# USB2RS485.net
KiCad netlist of a schematic drawn in Altium Designer
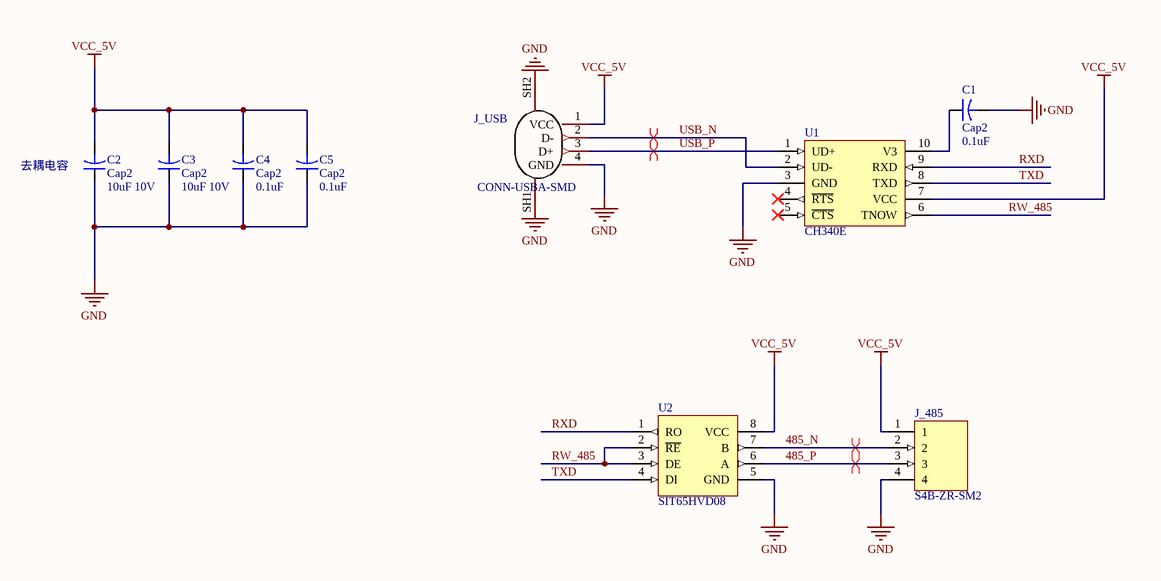
[diagram p0: USB2RS485.SchDoc]

(export (version "E")
  (design (tool "Eeschema 10.0.6"))
  (components
    (comp (ref "C1")
      (value "Cap2")
      (footprint "CAPR5-4X5")
      (description "Capacitor")
      (fields (field (name "ALTIUM_VALUE") "0.1uF") (field (name "PUBLISHER") "Altium Limited"))
      (libsource (lib "Miscellaneous Devices") (part "Cap2"))
    )
    (comp (ref "C2")
      (value "Cap2")
      (footprint "CAPR5-4X5")
      (description "Capacitor")
      (fields (field (name "ALTIUM_VALUE") "10uF 10V") (field (name "PUBLISHER") "Altium Limited"))
      (libsource (lib "Miscellaneous Devices") (part "Cap2"))
    )
    (comp (ref "C3")
      (value "Cap2")
      (footprint "CAPR5-4X5")
      (description "Capacitor")
      (fields (field (name "ALTIUM_VALUE") "10uF 10V") (field (name "PUBLISHER") "Altium Limited"))
      (libsource (lib "Miscellaneous Devices") (part "Cap2"))
    )
    (comp (ref "C4")
      (value "Cap2")
      (footprint "CAPR5-4X5")
      (description "Capacitor")
      (fields (field (name "ALTIUM_VALUE") "0.1uF") (field (name "PUBLISHER") "Altium Limited"))
      (libsource (lib "Miscellaneous Devices") (part "Cap2"))
    )
    (comp (ref "C5")
      (value "Cap2")
      (footprint "CAPR5-4X5")
      (description "Capacitor")
      (fields (field (name "ALTIUM_VALUE") "0.1uF") (field (name "PUBLISHER") "Altium Limited"))
      (libsource (lib "Miscellaneous Devices") (part "Cap2"))
    )
    (comp (ref "J_485") (value "S4B-ZR-SM2") (footprint "SM2") (libsource (lib "USB2RS485") (part "CONN4B")))
    (comp (ref "J_USB")
      (value "CONN-USBA-SMD")
      (footprint "USB-A-SMD_AF")
      (libsource (lib "USB2RS485") (part "CONN-USB"))
    )
    (comp (ref "U1") (value "CH340E") (footprint "MSOP10") (libsource (lib "USB2RS485") (part "CH340E")))
    (comp (ref "U2")
      (value "SIT65HVD08")
      (footprint "MSOP8")
      (libsource (lib "USB2RS485") (part "SIT65HVD08DGK"))
    )
  )
  (nets
    (net (code "1") (name "/485_N") (class "Default")
      (node (ref "J_485") (pin "2") (pinfunction "2_2") (pintype "input"))
      (node (ref "U2") (pin "7") (pinfunction "B_7") (pintype "output"))
    )
    (net (code "2") (name "/485_P") (class "Default")
      (node (ref "J_485") (pin "3") (pinfunction "3_3") (pintype "input"))
      (node (ref "U2") (pin "6") (pinfunction "A_6") (pintype "output"))
    )
    (net (code "3") (name "/RW_485") (class "Default")
      (node (ref "U1") (pin "6") (pinfunction "TNOW_6") (pintype "output"))
      (node (ref "U2") (pin "2") (pinfunction "~{RE}_2") (pintype "input"))
      (node (ref "U2") (pin "3") (pinfunction "DE_3") (pintype "input"))
    )
    (net (code "4") (name "/RXD") (class "Default")
      (node (ref "U1") (pin "9") (pinfunction "RXD_9") (pintype "input"))
      (node (ref "U2") (pin "1") (pinfunction "RO_1") (pintype "output"))
    )
    (net (code "5") (name "/TXD") (class "Default")
      (node (ref "U1") (pin "8") (pinfunction "TXD_8") (pintype "output"))
      (node (ref "U2") (pin "4") (pinfunction "DI_4") (pintype "input"))
    )
    (net (code "6") (name "/USB_N") (class "Default")
      (node (ref "J_USB") (pin "2") (pinfunction "D-_2") (pintype "output"))
      (node (ref "U1") (pin "2") (pinfunction "UD-_2") (pintype "input"))
    )
    (net (code "7") (name "/USB_P") (class "Default")
      (node (ref "J_USB") (pin "3") (pinfunction "D+_3") (pintype "output"))
      (node (ref "U1") (pin "1") (pinfunction "UD+_1") (pintype "input"))
    )
    (net (code "8") (name "GND") (class "Default")
      (node (ref "C1") (pin "2") (pinfunction "2_2") (pintype "passive"))
      (node (ref "C2") (pin "1") (pinfunction "1_1") (pintype "passive"))
      (node (ref "C3") (pin "1") (pinfunction "1_1") (pintype "passive"))
      (node (ref "C4") (pin "1") (pinfunction "1_1") (pintype "passive"))
      (node (ref "C5") (pin "1") (pinfunction "1_1") (pintype "passive"))
      (node (ref "J_485") (pin "4") (pinfunction "4_4") (pintype "power_in"))
      (node (ref "J_USB") (pin "4") (pinfunction "GND_4") (pintype "power_in"))
      (node (ref "J_USB") (pin "SH1") (pinfunction "SH1_SH1") (pintype "passive"))
      (node (ref "J_USB") (pin "SH2") (pinfunction "SH2_SH2") (pintype "passive"))
      (node (ref "U1") (pin "3") (pinfunction "GND_3") (pintype "power_in"))
      (node (ref "U2") (pin "5") (pinfunction "GND_5") (pintype "power_in"))
    )
    (net (code "9") (name "Net-(U1-V3)") (class "Default")
      (node (ref "C1") (pin "1") (pinfunction "1_1") (pintype "passive"))
      (node (ref "U1") (pin "10") (pinfunction "V3_10") (pintype "power_in"))
    )
    (net (code "10") (name "VCC_5V") (class "Default")
      (node (ref "C2") (pin "2") (pinfunction "2_2") (pintype "passive"))
      (node (ref "C3") (pin "2") (pinfunction "2_2") (pintype "passive"))
      (node (ref "C4") (pin "2") (pinfunction "2_2") (pintype "passive"))
      (node (ref "C5") (pin "2") (pinfunction "2_2") (pintype "passive"))
      (node (ref "J_485") (pin "1") (pinfunction "1_1") (pintype "power_in"))
      (node (ref "J_USB") (pin "1") (pinfunction "VCC_1") (pintype "power_in"))
      (node (ref "U1") (pin "7") (pinfunction "VCC_7") (pintype "power_in"))
      (node (ref "U2") (pin "8") (pinfunction "VCC_8") (pintype "power_in"))
    )
    (net (code "11") (name "unconnected-(U1-~{CTS}-Pad5)") (class "Default")
      (node (ref "U1") (pin "5") (pinfunction "~{CTS}_5") (pintype "input+no_connect"))
    )
    (net (code "12") (name "unconnected-(U1-~{RTS}-Pad4)") (class "Default")
      (node (ref "U1") (pin "4") (pinfunction "~{RTS}_4") (pintype "output+no_connect"))
    )
  )
)
